# ZynqPL.net
KiCad netlist of a schematic drawn in Altium Designer
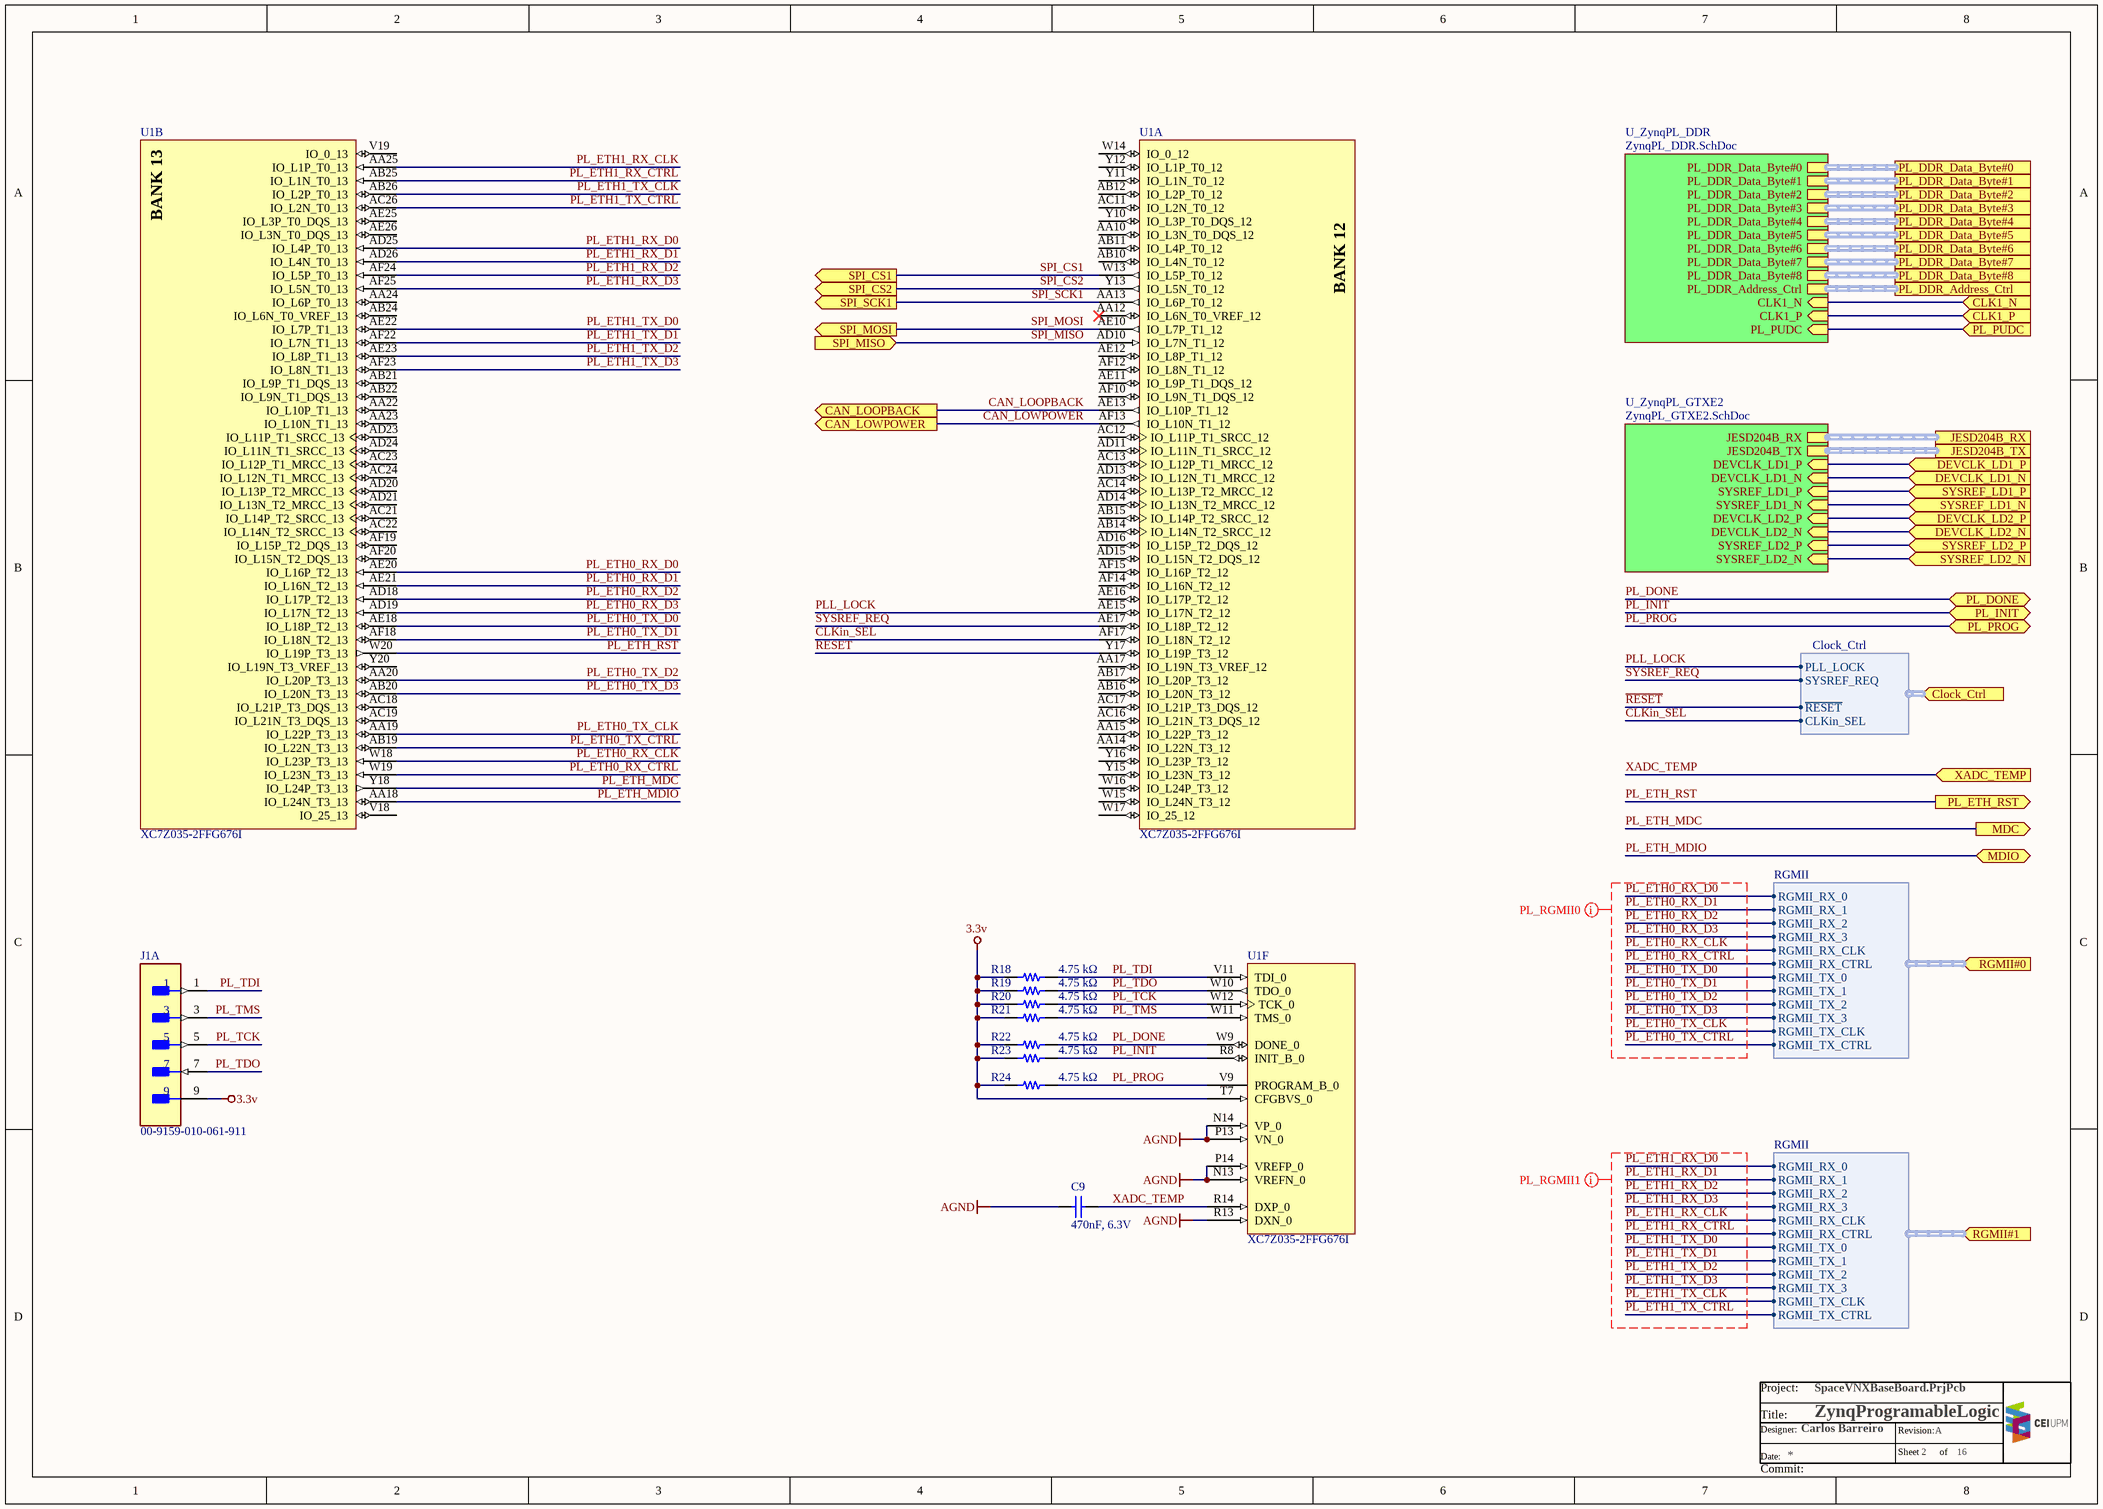
[diagram p0: ZynqPL.SchDoc]

(export (version "E")
  (design (tool "Eeschema 10.0.6"))
  (components
    (comp (ref "C9")
      (value "470nF, 6.3V")
      (footprint "WURTH_WCAP-CSGP_0402")
      (description "WCAP-CSGP Multilayer Ceramic Chip Capacitor, General Purpose, size 0402, X5R, 470nF, 6.3V")
      (fields
        (field (name "MANUFACTURER PART NUMBER") "885012105004")
        (field (name "MANUFACTURER") "Wurth Elektronik")
      )
      (libsource (lib "SpaceVNX") (part "885012105004"))
    )
    (comp (ref "J1")
      (value "00-9159-010-061-911")
      (footprint "KYOCERA_00-9159-010-061-911")
      (description "Coplanar Open Ended Card Edge Connector 10 Pin")
      (libsource (lib "SpaceVNX") (part "00-9159-010-061-911"))
    )
    (comp (ref "R18")
      (value "4.75 kΩ")
      (footprint "PANASONIC_ERJ2G_0402")
      (description "General Purpose Thick Film Chip Resistors")
      (fields (field (name "MANUFACTURER") "Panasonic"))
      (libsource (lib "SpaceVNX") (part "ERJ2RKF4751X"))
    )
    (comp (ref "R19")
      (value "4.75 kΩ")
      (footprint "PANASONIC_ERJ2G_0402")
      (description "General Purpose Thick Film Chip Resistors")
      (fields (field (name "MANUFACTURER") "Panasonic"))
      (libsource (lib "SpaceVNX") (part "ERJ2RKF4751X"))
    )
    (comp (ref "R20")
      (value "4.75 kΩ")
      (footprint "PANASONIC_ERJ2G_0402")
      (description "General Purpose Thick Film Chip Resistors")
      (fields (field (name "MANUFACTURER") "Panasonic"))
      (libsource (lib "SpaceVNX") (part "ERJ2RKF4751X"))
    )
    (comp (ref "R21")
      (value "4.75 kΩ")
      (footprint "PANASONIC_ERJ2G_0402")
      (description "General Purpose Thick Film Chip Resistors")
      (fields (field (name "MANUFACTURER") "Panasonic"))
      (libsource (lib "SpaceVNX") (part "ERJ2RKF4751X"))
    )
    (comp (ref "R22")
      (value "4.75 kΩ")
      (footprint "PANASONIC_ERJ2G_0402")
      (description "General Purpose Thick Film Chip Resistors")
      (fields (field (name "MANUFACTURER") "Panasonic"))
      (libsource (lib "SpaceVNX") (part "ERJ2RKF4751X"))
    )
    (comp (ref "R23")
      (value "4.75 kΩ")
      (footprint "PANASONIC_ERJ2G_0402")
      (description "General Purpose Thick Film Chip Resistors")
      (fields (field (name "MANUFACTURER") "Panasonic"))
      (libsource (lib "SpaceVNX") (part "ERJ2RKF4751X"))
    )
    (comp (ref "R24")
      (value "4.75 kΩ")
      (footprint "PANASONIC_ERJ2G_0402")
      (description "General Purpose Thick Film Chip Resistors")
      (fields (field (name "MANUFACTURER") "Panasonic"))
      (libsource (lib "SpaceVNX") (part "ERJ2RKF4751X"))
    )
    (comp (ref "U1")
      (value "XC7Z035-2FFG676I")
      (footprint "XILINX_FBG676")
      (fields (field (name "PARTNUMBER") "XC7Z035-2FBG676I") (field (name "GENERIC PART NUMBER") "XC7Z035"))
      (libsource (lib "") (part "XC7Z035-2FFG676I_2"))
    )
  )
  (nets
    (net (code "15") (name "/CAN_LOOPBACK") (class "Default")
      (node (ref "U1") (pin "AE13") (pinfunction "IO_L10P_T1_12_AE13") (pintype "output"))
    )
    (net (code "16") (name "/CAN_LOWPOWER") (class "Default")
      (node (ref "U1") (pin "AF13") (pinfunction "IO_L10N_T1_12_AF13") (pintype "output"))
    )
    (net (code "19") (name "/CLKin_SEL") (class "Default")
      (node (ref "U1") (pin "AF17") (pinfunction "IO_L18N_T2_12_AF17") (pintype "bidirectional"))
    )
    (net (code "26") (name "/PLL_LOCK") (class "Default")
      (node (ref "U1") (pin "AE15") (pinfunction "IO_L17N_T2_12_AE15") (pintype "bidirectional"))
    )
    (net (code "37") (name "/PL_DONE") (class "Default")
      (node (ref "R22") (pin "2") (pinfunction "2_2") (pintype "passive"))
      (node (ref "U1") (pin "W9") (pinfunction "DONE_0_W9") (pintype "bidirectional"))
    )
    (net (code "38") (name "/PL_ETH0_RX_CLK") (class "Default")
      (node (ref "U1") (pin "W18") (pinfunction "IO_L23P_T3_13_W18") (pintype "input"))
    )
    (net (code "39") (name "/PL_ETH0_RX_CTRL") (class "Default")
      (node (ref "U1") (pin "W19") (pinfunction "IO_L23N_T3_13_W19") (pintype "input"))
    )
    (net (code "40") (name "/PL_ETH0_RX_D0") (class "Default")
      (node (ref "U1") (pin "AE20") (pinfunction "IO_L16P_T2_13_AE20") (pintype "input"))
    )
    (net (code "41") (name "/PL_ETH0_RX_D1") (class "Default")
      (node (ref "U1") (pin "AE21") (pinfunction "IO_L16N_T2_13_AE21") (pintype "input"))
    )
    (net (code "42") (name "/PL_ETH0_RX_D2") (class "Default")
      (node (ref "U1") (pin "AD18") (pinfunction "IO_L17P_T2_13_AD18") (pintype "input"))
    )
    (net (code "43") (name "/PL_ETH0_RX_D3") (class "Default")
      (node (ref "U1") (pin "AD19") (pinfunction "IO_L17N_T2_13_AD19") (pintype "input"))
    )
    (net (code "44") (name "/PL_ETH0_TX_CLK") (class "Default")
      (node (ref "U1") (pin "AA19") (pinfunction "IO_L22P_T3_13_AA19") (pintype "bidirectional"))
    )
    (net (code "45") (name "/PL_ETH0_TX_CTRL") (class "Default")
      (node (ref "U1") (pin "AB19") (pinfunction "IO_L22N_T3_13_AB19") (pintype "bidirectional"))
    )
    (net (code "46") (name "/PL_ETH0_TX_D0") (class "Default")
      (node (ref "U1") (pin "AE18") (pinfunction "IO_L18P_T2_13_AE18") (pintype "bidirectional"))
    )
    (net (code "47") (name "/PL_ETH0_TX_D1") (class "Default")
      (node (ref "U1") (pin "AF18") (pinfunction "IO_L18N_T2_13_AF18") (pintype "bidirectional"))
    )
    (net (code "48") (name "/PL_ETH0_TX_D2") (class "Default")
      (node (ref "U1") (pin "AA20") (pinfunction "IO_L20P_T3_13_AA20") (pintype "bidirectional"))
    )
    (net (code "49") (name "/PL_ETH0_TX_D3") (class "Default")
      (node (ref "U1") (pin "AB20") (pinfunction "IO_L20N_T3_13_AB20") (pintype "bidirectional"))
    )
    (net (code "50") (name "/PL_ETH1_RX_CLK") (class "Default")
      (node (ref "U1") (pin "AA25") (pinfunction "IO_L1P_T0_13_AA25") (pintype "input"))
    )
    (net (code "51") (name "/PL_ETH1_RX_CTRL") (class "Default")
      (node (ref "U1") (pin "AB25") (pinfunction "IO_L1N_T0_13_AB25") (pintype "input"))
    )
    (net (code "52") (name "/PL_ETH1_RX_D0") (class "Default")
      (node (ref "U1") (pin "AD25") (pinfunction "IO_L4P_T0_13_AD25") (pintype "input"))
    )
    (net (code "53") (name "/PL_ETH1_RX_D1") (class "Default")
      (node (ref "U1") (pin "AD26") (pinfunction "IO_L4N_T0_13_AD26") (pintype "input"))
    )
    (net (code "54") (name "/PL_ETH1_RX_D2") (class "Default")
      (node (ref "U1") (pin "AF24") (pinfunction "IO_L5P_T0_13_AF24") (pintype "input"))
    )
    (net (code "55") (name "/PL_ETH1_RX_D3") (class "Default")
      (node (ref "U1") (pin "AF25") (pinfunction "IO_L5N_T0_13_AF25") (pintype "input"))
    )
    (net (code "56") (name "/PL_ETH1_TX_CLK") (class "Default")
      (node (ref "U1") (pin "AB26") (pinfunction "IO_L2P_T0_13_AB26") (pintype "bidirectional"))
    )
    (net (code "57") (name "/PL_ETH1_TX_CTRL") (class "Default")
      (node (ref "U1") (pin "AC26") (pinfunction "IO_L2N_T0_13_AC26") (pintype "bidirectional"))
    )
    (net (code "58") (name "/PL_ETH1_TX_D0") (class "Default")
      (node (ref "U1") (pin "AE22") (pinfunction "IO_L7P_T1_13_AE22") (pintype "bidirectional"))
    )
    (net (code "59") (name "/PL_ETH1_TX_D1") (class "Default")
      (node (ref "U1") (pin "AF22") (pinfunction "IO_L7N_T1_13_AF22") (pintype "bidirectional"))
    )
    (net (code "60") (name "/PL_ETH1_TX_D2") (class "Default")
      (node (ref "U1") (pin "AE23") (pinfunction "IO_L8P_T1_13_AE23") (pintype "bidirectional"))
    )
    (net (code "61") (name "/PL_ETH1_TX_D3") (class "Default")
      (node (ref "U1") (pin "AF23") (pinfunction "IO_L8N_T1_13_AF23") (pintype "bidirectional"))
    )
    (net (code "62") (name "/PL_ETH_MDC") (class "Default")
      (node (ref "U1") (pin "Y18") (pinfunction "IO_L24P_T3_13_Y18") (pintype "output"))
    )
    (net (code "63") (name "/PL_ETH_MDIO") (class "Default")
      (node (ref "U1") (pin "AA18") (pinfunction "IO_L24N_T3_13_AA18") (pintype "bidirectional"))
    )
    (net (code "64") (name "/PL_ETH_RST") (class "Default")
      (node (ref "U1") (pin "W20") (pinfunction "IO_L19P_T3_13_W20") (pintype "output"))
    )
    (net (code "65") (name "/PL_INIT") (class "Default")
      (node (ref "R23") (pin "2") (pinfunction "2_2") (pintype "passive"))
      (node (ref "U1") (pin "R8") (pinfunction "INIT_B_0_R8") (pintype "bidirectional"))
    )
    (net (code "66") (name "/PL_PROG") (class "Default")
      (node (ref "R24") (pin "2") (pinfunction "2_2") (pintype "passive"))
      (node (ref "U1") (pin "V9") (pinfunction "PROGRAM_B_0_V9") (pintype "passive"))
    )
    (net (code "68") (name "/PL_TCK") (class "Default")
      (node (ref "J1") (pin "5") (pinfunction "5_5") (pintype "output"))
      (node (ref "R20") (pin "2") (pinfunction "2_2") (pintype "passive"))
      (node (ref "U1") (pin "W12") (pinfunction "TCK_0_W12") (pintype "input"))
    )
    (net (code "69") (name "/PL_TDI") (class "Default")
      (node (ref "J1") (pin "1") (pinfunction "1_1") (pintype "output"))
      (node (ref "R18") (pin "2") (pinfunction "2_2") (pintype "passive"))
      (node (ref "U1") (pin "V11") (pinfunction "TDI_0_V11") (pintype "input"))
    )
    (net (code "70") (name "/PL_TDO") (class "Default")
      (node (ref "J1") (pin "7") (pinfunction "7_7") (pintype "input"))
      (node (ref "R19") (pin "2") (pinfunction "2_2") (pintype "passive"))
      (node (ref "U1") (pin "W10") (pinfunction "TDO_0_W10") (pintype "output"))
    )
    (net (code "71") (name "/PL_TMS") (class "Default")
      (node (ref "J1") (pin "3") (pinfunction "3_3") (pintype "output"))
      (node (ref "R21") (pin "2") (pinfunction "2_2") (pintype "passive"))
      (node (ref "U1") (pin "W11") (pinfunction "TMS_0_W11") (pintype "input"))
    )
    (net (code "72") (name "/SPI_CS1") (class "Default")
      (node (ref "U1") (pin "W13") (pinfunction "IO_L5P_T0_12_W13") (pintype "output"))
    )
    (net (code "73") (name "/SPI_CS2") (class "Default")
      (node (ref "U1") (pin "Y13") (pinfunction "IO_L5N_T0_12_Y13") (pintype "output"))
    )
    (net (code "74") (name "/SPI_MISO") (class "Default")
      (node (ref "U1") (pin "AD10") (pinfunction "IO_L7N_T1_12_AD10") (pintype "input"))
    )
    (net (code "75") (name "/SPI_MOSI") (class "Default")
      (node (ref "U1") (pin "AE10") (pinfunction "IO_L7P_T1_12_AE10") (pintype "output"))
    )
    (net (code "76") (name "/SPI_SCK1") (class "Default")
      (node (ref "U1") (pin "AA13") (pinfunction "IO_L6P_T0_12_AA13") (pintype "output"))
    )
    (net (code "81") (name "/SYSREF_REQ") (class "Default")
      (node (ref "U1") (pin "AE17") (pinfunction "IO_L18P_T2_12_AE17") (pintype "bidirectional"))
    )
    (net (code "82") (name "/XADC_TEMP") (class "Default")
      (node (ref "C9") (pin "2") (pinfunction "2_2") (pintype "passive"))
      (node (ref "U1") (pin "R14") (pinfunction "DXP_0_R14") (pintype "input"))
    )
    (net (code "85") (name "/~{RESET}") (class "Default")
      (node (ref "U1") (pin "Y17") (pinfunction "IO_L19P_T3_12_Y17") (pintype "bidirectional"))
    )
    (net (code "86") (name "3.3v") (class "Default")
      (node (ref "J1") (pin "9") (pinfunction "9_9") (pintype "power_in"))
      (node (ref "R18") (pin "1") (pinfunction "1_1") (pintype "passive"))
      (node (ref "R19") (pin "1") (pinfunction "1_1") (pintype "passive"))
      (node (ref "R20") (pin "1") (pinfunction "1_1") (pintype "passive"))
      (node (ref "R21") (pin "1") (pinfunction "1_1") (pintype "passive"))
      (node (ref "R22") (pin "1") (pinfunction "1_1") (pintype "passive"))
      (node (ref "R23") (pin "1") (pinfunction "1_1") (pintype "passive"))
      (node (ref "R24") (pin "1") (pinfunction "1_1") (pintype "passive"))
      (node (ref "U1") (pin "T7") (pinfunction "CFGBVS_0_T7") (pintype "input"))
    )
    (net (code "87") (name "AGND") (class "Default")
      (node (ref "C9") (pin "1") (pinfunction "1_1") (pintype "passive"))
      (node (ref "U1") (pin "N13") (pinfunction "VREFN_0_N13") (pintype "input"))
      (node (ref "U1") (pin "N14") (pinfunction "VP_0_N14") (pintype "input"))
      (node (ref "U1") (pin "P13") (pinfunction "VN_0_P13") (pintype "input"))
      (node (ref "U1") (pin "P14") (pinfunction "VREFP_0_P14") (pintype "input"))
      (node (ref "U1") (pin "R13") (pinfunction "DXN_0_R13") (pintype "input"))
    )
    (net (code "88") (name "unconnected-(U1A-IO_0_12-PadW14)") (class "Default")
      (node (ref "U1") (pin "W14") (pinfunction "IO_0_12_W14") (pintype "bidirectional"))
    )
    (net (code "89") (name "unconnected-(U1A-IO_25_12-PadW17)") (class "Default")
      (node (ref "U1") (pin "W17") (pinfunction "IO_25_12_W17") (pintype "bidirectional"))
    )
    (net (code "90") (name "unconnected-(U1A-IO_L1N_T0_12-PadY11)") (class "Default")
      (node (ref "U1") (pin "Y11") (pinfunction "IO_L1N_T0_12_Y11") (pintype "bidirectional"))
    )
    (net (code "91") (name "unconnected-(U1A-IO_L1P_T0_12-PadY12)") (class "Default")
      (node (ref "U1") (pin "Y12") (pinfunction "IO_L1P_T0_12_Y12") (pintype "bidirectional"))
    )
    (net (code "92") (name "unconnected-(U1A-IO_L2N_T0_12-PadAC11)") (class "Default")
      (node (ref "U1") (pin "AC11") (pinfunction "IO_L2N_T0_12_AC11") (pintype "bidirectional"))
    )
    (net (code "93") (name "unconnected-(U1A-IO_L2P_T0_12-PadAB12)") (class "Default")
      (node (ref "U1") (pin "AB12") (pinfunction "IO_L2P_T0_12_AB12") (pintype "bidirectional"))
    )
    (net (code "94") (name "unconnected-(U1A-IO_L3N_T0_DQS_12-PadAA10)") (class "Default")
      (node (ref "U1") (pin "AA10") (pinfunction "IO_L3N_T0_DQS_12_AA10") (pintype "bidirectional"))
    )
    (net (code "95") (name "unconnected-(U1A-IO_L3P_T0_DQS_12-PadY10)") (class "Default")
      (node (ref "U1") (pin "Y10") (pinfunction "IO_L3P_T0_DQS_12_Y10") (pintype "bidirectional"))
    )
    (net (code "96") (name "unconnected-(U1A-IO_L4N_T0_12-PadAB10)") (class "Default")
      (node (ref "U1") (pin "AB10") (pinfunction "IO_L4N_T0_12_AB10") (pintype "bidirectional"))
    )
    (net (code "97") (name "unconnected-(U1A-IO_L4P_T0_12-PadAB11)") (class "Default")
      (node (ref "U1") (pin "AB11") (pinfunction "IO_L4P_T0_12_AB11") (pintype "bidirectional"))
    )
    (net (code "98") (name "unconnected-(U1A-IO_L6N_T0_VREF_12-PadAA12)") (class "Default")
      (node (ref "U1") (pin "AA12") (pinfunction "IO_L6N_T0_VREF_12_AA12") (pintype "bidirectional+no_connect"))
    )
    (net (code "99") (name "unconnected-(U1A-IO_L8N_T1_12-PadAF12)") (class "Default")
      (node (ref "U1") (pin "AF12") (pinfunction "IO_L8N_T1_12_AF12") (pintype "bidirectional"))
    )
    (net (code "100") (name "unconnected-(U1A-IO_L8P_T1_12-PadAE12)") (class "Default")
      (node (ref "U1") (pin "AE12") (pinfunction "IO_L8P_T1_12_AE12") (pintype "bidirectional"))
    )
    (net (code "101") (name "unconnected-(U1A-IO_L9N_T1_DQS_12-PadAF10)") (class "Default")
      (node (ref "U1") (pin "AF10") (pinfunction "IO_L9N_T1_DQS_12_AF10") (pintype "bidirectional"))
    )
    (net (code "102") (name "unconnected-(U1A-IO_L9P_T1_DQS_12-PadAE11)") (class "Default")
      (node (ref "U1") (pin "AE11") (pinfunction "IO_L9P_T1_DQS_12_AE11") (pintype "bidirectional"))
    )
    (net (code "103") (name "unconnected-(U1A-IO_L11N_T1_SRCC_12-PadAD11)") (class "Default")
      (node (ref "U1") (pin "AD11") (pinfunction "IO_L11N_T1_SRCC_12_AD11") (pintype "bidirectional"))
    )
    (net (code "104") (name "unconnected-(U1A-IO_L11P_T1_SRCC_12-PadAC12)") (class "Default")
      (node (ref "U1") (pin "AC12") (pinfunction "IO_L11P_T1_SRCC_12_AC12") (pintype "bidirectional"))
    )
    (net (code "105") (name "unconnected-(U1A-IO_L12N_T1_MRCC_12-PadAD13)") (class "Default")
      (node (ref "U1") (pin "AD13") (pinfunction "IO_L12N_T1_MRCC_12_AD13") (pintype "bidirectional"))
    )
    (net (code "106") (name "unconnected-(U1A-IO_L12P_T1_MRCC_12-PadAC13)") (class "Default")
      (node (ref "U1") (pin "AC13") (pinfunction "IO_L12P_T1_MRCC_12_AC13") (pintype "bidirectional"))
    )
    (net (code "107") (name "unconnected-(U1A-IO_L13N_T2_MRCC_12-PadAD14)") (class "Default")
      (node (ref "U1") (pin "AD14") (pinfunction "IO_L13N_T2_MRCC_12_AD14") (pintype "bidirectional"))
    )
    (net (code "108") (name "unconnected-(U1A-IO_L13P_T2_MRCC_12-PadAC14)") (class "Default")
      (node (ref "U1") (pin "AC14") (pinfunction "IO_L13P_T2_MRCC_12_AC14") (pintype "bidirectional"))
    )
    (net (code "109") (name "unconnected-(U1A-IO_L14N_T2_SRCC_12-PadAB14)") (class "Default")
      (node (ref "U1") (pin "AB14") (pinfunction "IO_L14N_T2_SRCC_12_AB14") (pintype "bidirectional"))
    )
    (net (code "110") (name "unconnected-(U1A-IO_L14P_T2_SRCC_12-PadAB15)") (class "Default")
      (node (ref "U1") (pin "AB15") (pinfunction "IO_L14P_T2_SRCC_12_AB15") (pintype "bidirectional"))
    )
    (net (code "111") (name "unconnected-(U1A-IO_L15N_T2_DQS_12-PadAD15)") (class "Default")
      (node (ref "U1") (pin "AD15") (pinfunction "IO_L15N_T2_DQS_12_AD15") (pintype "bidirectional"))
    )
    (net (code "112") (name "unconnected-(U1A-IO_L15P_T2_DQS_12-PadAD16)") (class "Default")
      (node (ref "U1") (pin "AD16") (pinfunction "IO_L15P_T2_DQS_12_AD16") (pintype "bidirectional"))
    )
    (net (code "113") (name "unconnected-(U1A-IO_L16N_T2_12-PadAF14)") (class "Default")
      (node (ref "U1") (pin "AF14") (pinfunction "IO_L16N_T2_12_AF14") (pintype "bidirectional"))
    )
    (net (code "114") (name "unconnected-(U1A-IO_L16P_T2_12-PadAF15)") (class "Default")
      (node (ref "U1") (pin "AF15") (pinfunction "IO_L16P_T2_12_AF15") (pintype "bidirectional"))
    )
    (net (code "115") (name "unconnected-(U1A-IO_L17P_T2_12-PadAE16)") (class "Default")
      (node (ref "U1") (pin "AE16") (pinfunction "IO_L17P_T2_12_AE16") (pintype "bidirectional"))
    )
    (net (code "116") (name "unconnected-(U1A-IO_L19N_T3_VREF_12-PadAA17)") (class "Default")
      (node (ref "U1") (pin "AA17") (pinfunction "IO_L19N_T3_VREF_12_AA17") (pintype "bidirectional"))
    )
    (net (code "117") (name "unconnected-(U1A-IO_L20N_T3_12-PadAB16)") (class "Default")
      (node (ref "U1") (pin "AB16") (pinfunction "IO_L20N_T3_12_AB16") (pintype "bidirectional"))
    )
    (net (code "118") (name "unconnected-(U1A-IO_L20P_T3_12-PadAB17)") (class "Default")
      (node (ref "U1") (pin "AB17") (pinfunction "IO_L20P_T3_12_AB17") (pintype "bidirectional"))
    )
    (net (code "119") (name "unconnected-(U1A-IO_L21N_T3_DQS_12-PadAC16)") (class "Default")
      (node (ref "U1") (pin "AC16") (pinfunction "IO_L21N_T3_DQS_12_AC16") (pintype "bidirectional"))
    )
    (net (code "120") (name "unconnected-(U1A-IO_L21P_T3_DQS_12-PadAC17)") (class "Default")
      (node (ref "U1") (pin "AC17") (pinfunction "IO_L21P_T3_DQS_12_AC17") (pintype "bidirectional"))
    )
    (net (code "121") (name "unconnected-(U1A-IO_L22N_T3_12-PadAA14)") (class "Default")
      (node (ref "U1") (pin "AA14") (pinfunction "IO_L22N_T3_12_AA14") (pintype "bidirectional"))
    )
    (net (code "122") (name "unconnected-(U1A-IO_L22P_T3_12-PadAA15)") (class "Default")
      (node (ref "U1") (pin "AA15") (pinfunction "IO_L22P_T3_12_AA15") (pintype "bidirectional"))
    )
    (net (code "123") (name "unconnected-(U1A-IO_L23N_T3_12-PadY15)") (class "Default")
      (node (ref "U1") (pin "Y15") (pinfunction "IO_L23N_T3_12_Y15") (pintype "bidirectional"))
    )
    (net (code "124") (name "unconnected-(U1A-IO_L23P_T3_12-PadY16)") (class "Default")
      (node (ref "U1") (pin "Y16") (pinfunction "IO_L23P_T3_12_Y16") (pintype "bidirectional"))
    )
    (net (code "125") (name "unconnected-(U1A-IO_L24N_T3_12-PadW15)") (class "Default")
      (node (ref "U1") (pin "W15") (pinfunction "IO_L24N_T3_12_W15") (pintype "bidirectional"))
    )
    (net (code "126") (name "unconnected-(U1A-IO_L24P_T3_12-PadW16)") (class "Default")
      (node (ref "U1") (pin "W16") (pinfunction "IO_L24P_T3_12_W16") (pintype "bidirectional"))
    )
    (net (code "127") (name "unconnected-(U1B-IO_0_13-PadV19)") (class "Default")
      (node (ref "U1") (pin "V19") (pinfunction "IO_0_13_V19") (pintype "bidirectional"))
    )
    (net (code "128") (name "unconnected-(U1B-IO_25_13-PadV18)") (class "Default")
      (node (ref "U1") (pin "V18") (pinfunction "IO_25_13_V18") (pintype "bidirectional"))
    )
    (net (code "129") (name "unconnected-(U1B-IO_L3N_T0_DQS_13-PadAE26)") (class "Default")
      (node (ref "U1") (pin "AE26") (pinfunction "IO_L3N_T0_DQS_13_AE26") (pintype "bidirectional"))
    )
    (net (code "130") (name "unconnected-(U1B-IO_L3P_T0_DQS_13-PadAE25)") (class "Default")
      (node (ref "U1") (pin "AE25") (pinfunction "IO_L3P_T0_DQS_13_AE25") (pintype "bidirectional"))
    )
    (net (code "131") (name "unconnected-(U1B-IO_L6N_T0_VREF_13-PadAB24)") (class "Default")
      (node (ref "U1") (pin "AB24") (pinfunction "IO_L6N_T0_VREF_13_AB24") (pintype "bidirectional"))
    )
    (net (code "132") (name "unconnected-(U1B-IO_L6P_T0_13-PadAA24)") (class "Default")
      (node (ref "U1") (pin "AA24") (pinfunction "IO_L6P_T0_13_AA24") (pintype "bidirectional"))
    )
    (net (code "133") (name "unconnected-(U1B-IO_L9N_T1_DQS_13-PadAB22)") (class "Default")
      (node (ref "U1") (pin "AB22") (pinfunction "IO_L9N_T1_DQS_13_AB22") (pintype "bidirectional"))
    )
    (net (code "134") (name "unconnected-(U1B-IO_L9P_T1_DQS_13-PadAB21)") (class "Default")
      (node (ref "U1") (pin "AB21") (pinfunction "IO_L9P_T1_DQS_13_AB21") (pintype "bidirectional"))
    )
    (net (code "135") (name "unconnected-(U1B-IO_L10N_T1_13-PadAA23)") (class "Default")
      (node (ref "U1") (pin "AA23") (pinfunction "IO_L10N_T1_13_AA23") (pintype "bidirectional"))
    )
    (net (code "136") (name "unconnected-(U1B-IO_L10P_T1_13-PadAA22)") (class "Default")
      (node (ref "U1") (pin "AA22") (pinfunction "IO_L10P_T1_13_AA22") (pintype "bidirectional"))
    )
    (net (code "137") (name "unconnected-(U1B-IO_L11N_T1_SRCC_13-PadAD24)") (class "Default")
      (node (ref "U1") (pin "AD24") (pinfunction "IO_L11N_T1_SRCC_13_AD24") (pintype "bidirectional"))
    )
    (net (code "138") (name "unconnected-(U1B-IO_L11P_T1_SRCC_13-PadAD23)") (class "Default")
      (node (ref "U1") (pin "AD23") (pinfunction "IO_L11P_T1_SRCC_13_AD23") (pintype "bidirectional"))
    )
    (net (code "139") (name "unconnected-(U1B-IO_L12N_T1_MRCC_13-PadAC24)") (class "Default")
      (node (ref "U1") (pin "AC24") (pinfunction "IO_L12N_T1_MRCC_13_AC24") (pintype "bidirectional"))
    )
    (net (code "140") (name "unconnected-(U1B-IO_L12P_T1_MRCC_13-PadAC23)") (class "Default")
      (node (ref "U1") (pin "AC23") (pinfunction "IO_L12P_T1_MRCC_13_AC23") (pintype "bidirectional"))
    )
    (net (code "141") (name "unconnected-(U1B-IO_L13N_T2_MRCC_13-PadAD21)") (class "Default")
      (node (ref "U1") (pin "AD21") (pinfunction "IO_L13N_T2_MRCC_13_AD21") (pintype "bidirectional"))
    )
    (net (code "142") (name "unconnected-(U1B-IO_L13P_T2_MRCC_13-PadAD20)") (class "Default")
      (node (ref "U1") (pin "AD20") (pinfunction "IO_L13P_T2_MRCC_13_AD20") (pintype "bidirectional"))
    )
    (net (code "143") (name "unconnected-(U1B-IO_L14N_T2_SRCC_13-PadAC22)") (class "Default")
      (node (ref "U1") (pin "AC22") (pinfunction "IO_L14N_T2_SRCC_13_AC22") (pintype "bidirectional"))
    )
    (net (code "144") (name "unconnected-(U1B-IO_L14P_T2_SRCC_13-PadAC21)") (class "Default")
      (node (ref "U1") (pin "AC21") (pinfunction "IO_L14P_T2_SRCC_13_AC21") (pintype "bidirectional"))
    )
    (net (code "145") (name "unconnected-(U1B-IO_L15N_T2_DQS_13-PadAF20)") (class "Default")
      (node (ref "U1") (pin "AF20") (pinfunction "IO_L15N_T2_DQS_13_AF20") (pintype "bidirectional"))
    )
    (net (code "146") (name "unconnected-(U1B-IO_L15P_T2_DQS_13-PadAF19)") (class "Default")
      (node (ref "U1") (pin "AF19") (pinfunction "IO_L15P_T2_DQS_13_AF19") (pintype "bidirectional"))
    )
    (net (code "147") (name "unconnected-(U1B-IO_L19N_T3_VREF_13-PadY20)") (class "Default")
      (node (ref "U1") (pin "Y20") (pinfunction "IO_L19N_T3_VREF_13_Y20") (pintype "bidirectional"))
    )
    (net (code "148") (name "unconnected-(U1B-IO_L21N_T3_DQS_13-PadAC19)") (class "Default")
      (node (ref "U1") (pin "AC19") (pinfunction "IO_L21N_T3_DQS_13_AC19") (pintype "bidirectional"))
    )
    (net (code "149") (name "unconnected-(U1B-IO_L21P_T3_DQS_13-PadAC18)") (class "Default")
      (node (ref "U1") (pin "AC18") (pinfunction "IO_L21P_T3_DQS_13_AC18") (pintype "bidirectional"))
    )
  )
)
